# cfs_5.net
KiCad netlist of a schematic drawn in EAGLE
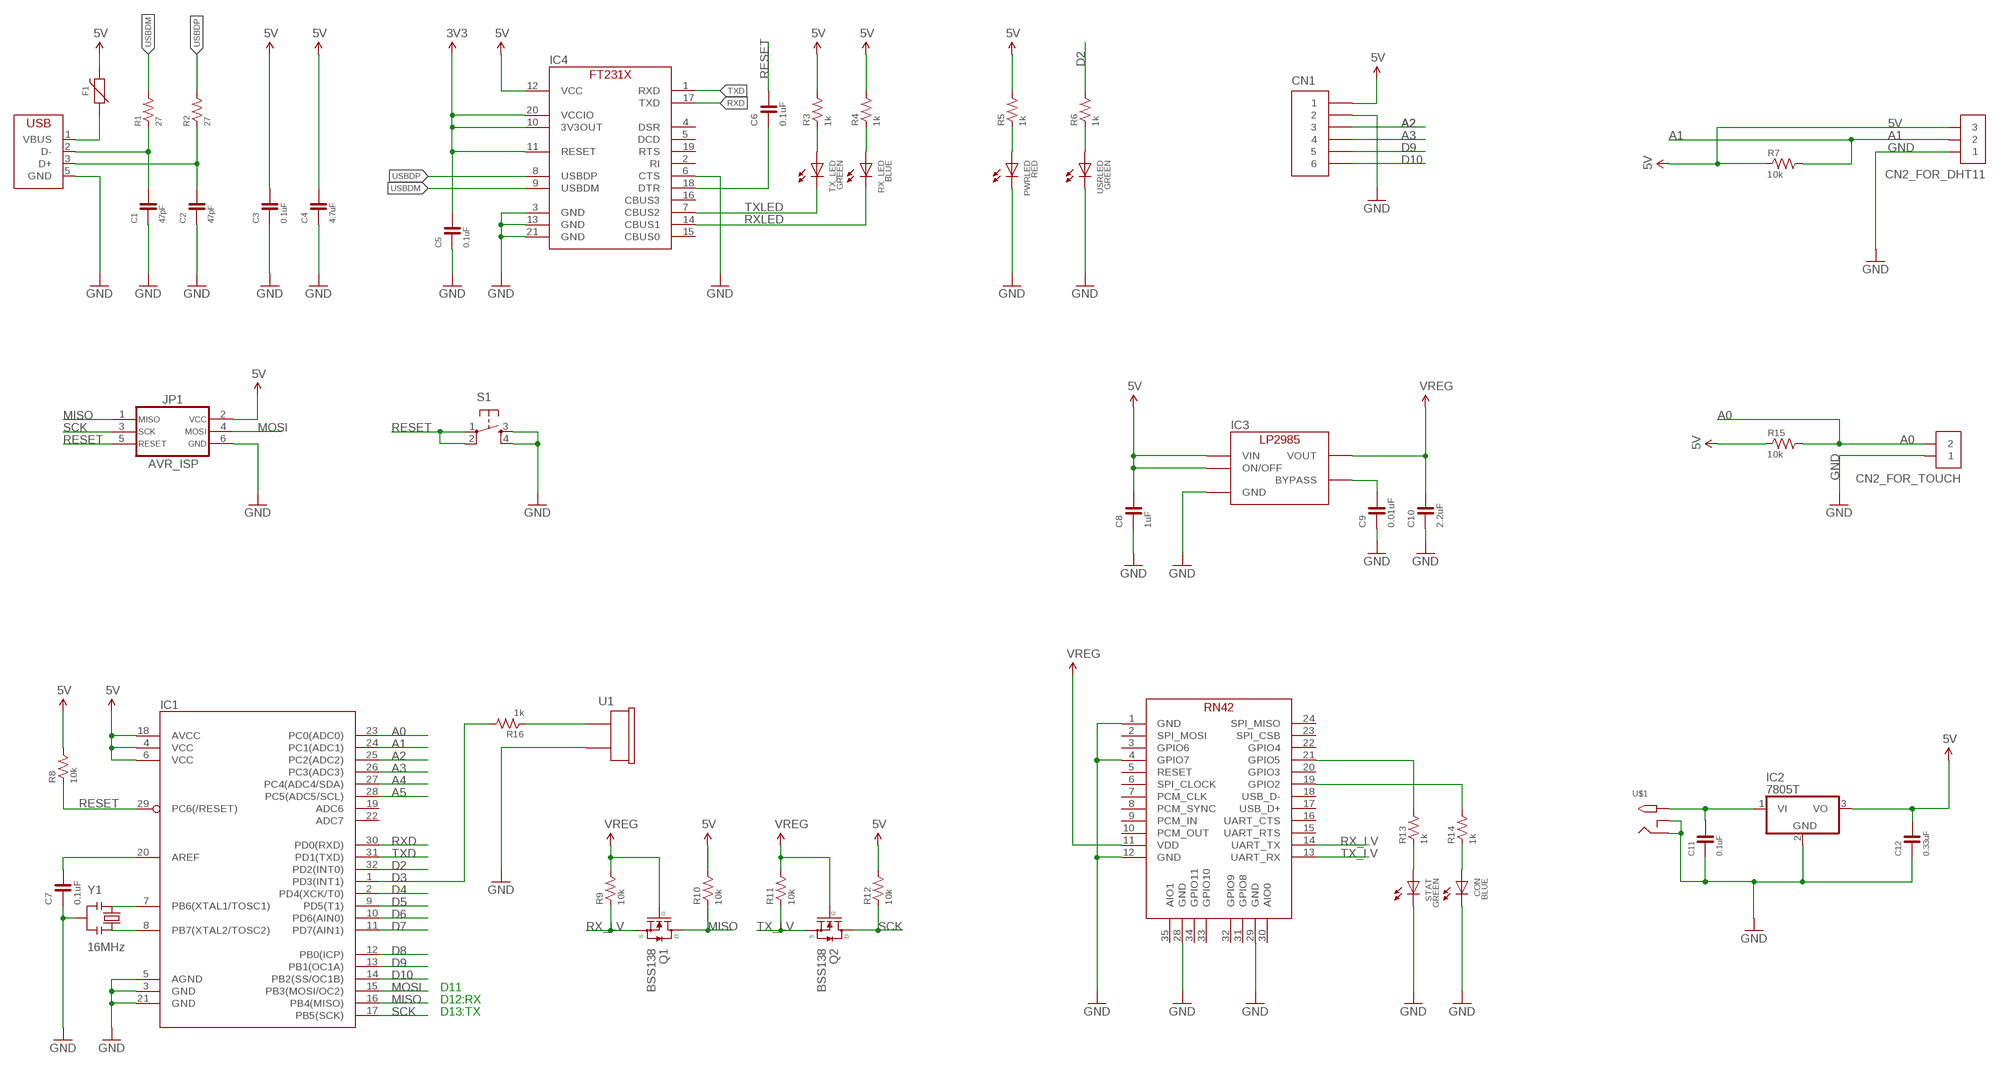
[diagram p0: schematic, sheet 1]

(export (version "E")
  (design (tool "Eeschema 10.0.6"))
  (components
    (comp (ref "C1")
      (value "47pF")
      (footprint "eagle-import:EIA0603")
      (libsource (lib "eagle-import") (part "u-aizu_CAPACITOR-0603"))
    )
    (comp (ref "C2")
      (value "47pF")
      (footprint "eagle-import:EIA0603")
      (libsource (lib "eagle-import") (part "u-aizu_CAPACITOR-0603"))
    )
    (comp (ref "C3")
      (value "0.1uF")
      (footprint "eagle-import:EIA0603")
      (libsource (lib "eagle-import") (part "u-aizu_CAPACITOR-0603"))
    )
    (comp (ref "C4")
      (value "4.7uF")
      (footprint "eagle-import:EIA0603")
      (libsource (lib "eagle-import") (part "u-aizu_CAPACITOR-0603"))
    )
    (comp (ref "C5")
      (value "0.1uF")
      (footprint "eagle-import:EIA0603")
      (libsource (lib "eagle-import") (part "u-aizu_CAPACITOR-0603"))
    )
    (comp (ref "C6")
      (value "0.1uF")
      (footprint "eagle-import:0603")
      (libsource (lib "eagle-import") (part "CAPACITOR-0603"))
    )
    (comp (ref "C7")
      (value "0.1uF")
      (footprint "eagle-import:0603")
      (libsource (lib "eagle-import") (part "CAPACITOR-0603"))
    )
    (comp (ref "C8")
      (value "1uF")
      (footprint "eagle-import:0603")
      (libsource (lib "eagle-import") (part "CAPACITOR-0603"))
    )
    (comp (ref "C9")
      (value "0.01uF")
      (footprint "eagle-import:0603")
      (libsource (lib "eagle-import") (part "CAPACITOR-0603"))
    )
    (comp (ref "C10")
      (value "2.2uF")
      (footprint "eagle-import:0603")
      (libsource (lib "eagle-import") (part "CAPACITOR-0603"))
    )
    (comp (ref "C11")
      (value "0.1uF")
      (footprint "eagle-import:EIA0603")
      (libsource (lib "eagle-import") (part "u-aizu_CAPACITOR-0603"))
    )
    (comp (ref "C12")
      (value "0.33uF")
      (footprint "eagle-import:EIA0603")
      (libsource (lib "eagle-import") (part "u-aizu_CAPACITOR-0603"))
    )
    (comp (ref "CN1")
      (value "PIN_HEADER_1X6")
      (footprint "eagle-import:PIN_1X6")
      (libsource (lib "eagle-import") (part "PIN_HEADER_1X6"))
    )
    (comp (ref "CN2_FOR_DHT11")
      (value "PIN_HEADER_1X3")
      (footprint "eagle-import:PIN_1X3")
      (libsource (lib "eagle-import") (part "PIN_HEADER_1X3"))
    )
    (comp (ref "CN2_FOR_TOUCH")
      (value "PIN_HEADER_1X2")
      (footprint "eagle-import:PIN_1X2")
      (libsource (lib "eagle-import") (part "PIN_HEADER_1X2"))
    )
    (comp (ref "CON")
      (value "BLUE")
      (footprint "eagle-import:0603")
      (libsource (lib "eagle-import") (part "LED-0603"))
    )
    (comp (ref "F1")
      (value "FUSE-NANO")
      (footprint "eagle-import:NANOSMDC035F")
      (libsource (lib "eagle-import") (part "FUSE-NANO"))
    )
    (comp (ref "IC1")
      (value "ATMEGA328P-AU")
      (footprint "eagle-import:TQFP-32")
      (libsource (lib "eagle-import") (part "ATMEGA328P-AU"))
    )
    (comp (ref "IC2")
      (value "7805T")
      (footprint "eagle-import:TO220H")
      (libsource (lib "eagle-import") (part "78T05"))
    )
    (comp (ref "IC3")
      (value "LP2985-33DBV")
      (footprint "eagle-import:SOT-23-5")
      (libsource (lib "eagle-import") (part "LP2985-33DBV"))
    )
    (comp (ref "IC4")
      (value "FT231XQ")
      (footprint "eagle-import:QFN-20_FT231X")
      (libsource (lib "eagle-import") (part "FT231XQ"))
    )
    (comp (ref "JP1")
      (value "AVR_ISP")
      (footprint "eagle-import:TC2030")
      (libsource (lib "eagle-import") (part "AVR_ISP-TC2030_NOHOLE"))
    )
    (comp (ref "PWRLED")
      (value "RED")
      (footprint "eagle-import:0603")
      (libsource (lib "eagle-import") (part "LED-0603"))
    )
    (comp (ref "Q1")
      (value "BSS138")
      (footprint "eagle-import:SOT23-3")
      (libsource (lib "eagle-import") (part "MOSFET-N"))
    )
    (comp (ref "Q2")
      (value "BSS138")
      (footprint "eagle-import:SOT23-3")
      (libsource (lib "eagle-import") (part "MOSFET-N"))
    )
    (comp (ref "R1")
      (value "27")
      (footprint "eagle-import:EIA0603")
      (libsource (lib "eagle-import") (part "u-aizu_RESISTOR-0603"))
    )
    (comp (ref "R2")
      (value "27")
      (footprint "eagle-import:EIA0603")
      (libsource (lib "eagle-import") (part "u-aizu_RESISTOR-0603"))
    )
    (comp (ref "R3")
      (value "1k")
      (footprint "eagle-import:0603")
      (libsource (lib "eagle-import") (part "RESISTOR-0603"))
    )
    (comp (ref "R4")
      (value "1k")
      (footprint "eagle-import:0603")
      (libsource (lib "eagle-import") (part "RESISTOR-0603"))
    )
    (comp (ref "R5")
      (value "1k")
      (footprint "eagle-import:0603")
      (libsource (lib "eagle-import") (part "RESISTOR-0603"))
    )
    (comp (ref "R6")
      (value "1k")
      (footprint "eagle-import:0603")
      (libsource (lib "eagle-import") (part "RESISTOR-0603"))
    )
    (comp (ref "R7")
      (value "10k")
      (footprint "eagle-import:0603")
      (libsource (lib "eagle-import") (part "RESISTOR-0603"))
    )
    (comp (ref "R8")
      (value "10k")
      (footprint "eagle-import:0603")
      (libsource (lib "eagle-import") (part "RESISTOR-0603"))
    )
    (comp (ref "R9")
      (value "10k")
      (footprint "eagle-import:0603")
      (libsource (lib "eagle-import") (part "RESISTOR-0603"))
    )
    (comp (ref "R10")
      (value "10k")
      (footprint "eagle-import:0603")
      (libsource (lib "eagle-import") (part "RESISTOR-0603"))
    )
    (comp (ref "R11")
      (value "10k")
      (footprint "eagle-import:0603")
      (libsource (lib "eagle-import") (part "RESISTOR-0603"))
    )
    (comp (ref "R12")
      (value "10k")
      (footprint "eagle-import:0603")
      (libsource (lib "eagle-import") (part "RESISTOR-0603"))
    )
    (comp (ref "R13")
      (value "1k")
      (footprint "eagle-import:0603")
      (libsource (lib "eagle-import") (part "RESISTOR-0603"))
    )
    (comp (ref "R14")
      (value "1k")
      (footprint "eagle-import:0603")
      (libsource (lib "eagle-import") (part "RESISTOR-0603"))
    )
    (comp (ref "R15")
      (value "10k")
      (footprint "eagle-import:0603")
      (libsource (lib "eagle-import") (part "RESISTOR-0603"))
    )
    (comp (ref "R16")
      (value "1k")
      (footprint "eagle-import:0603")
      (libsource (lib "eagle-import") (part "RESISTOR-0603"))
    )
    (comp (ref "RX_LED")
      (value "BLUE")
      (footprint "eagle-import:0603")
      (libsource (lib "eagle-import") (part "LED-0603"))
    )
    (comp (ref "S1")
      (value "TACT-SWITCH-SMD_KMR2")
      (footprint "eagle-import:KMR2")
      (libsource (lib "eagle-import") (part "TACT-SWITCH-SMD_KMR2"))
    )
    (comp (ref "STAT")
      (value "GREEN")
      (footprint "eagle-import:0603")
      (libsource (lib "eagle-import") (part "LED-0603"))
    )
    (comp (ref "TX_LED")
      (value "GREEN")
      (footprint "eagle-import:0603")
      (libsource (lib "eagle-import") (part "LED-0603"))
    )
    (comp (ref "U$1")
      (value "2.1MMJACKTHM")
      (footprint "eagle-import:PJ-102A")
      (libsource (lib "eagle-import") (part "2.1MMJACKTHM"))
    )
    (comp (ref "U$4")
      (value "MICROCHIP-RN42")
      (footprint "eagle-import:MICROCHIP-RN42")
      (libsource (lib "eagle-import") (part "MICROCHIP-RN42"))
    )
    (comp (ref "U1")
      (value "BUZZER")
      (footprint "eagle-import:PKM13EPYH4000-A0")
      (libsource (lib "eagle-import") (part "BUZZER"))
    )
    (comp (ref "USB1")
      (value "USB-MICRO_B_SMT_HIROSE")
      (footprint "eagle-import:ZX62R-B-5P")
      (libsource (lib "eagle-import") (part "USB-MICRO_B_SMT_HIROSE"))
    )
    (comp (ref "USRLED")
      (value "GREEN")
      (footprint "eagle-import:0603")
      (libsource (lib "eagle-import") (part "LED-0603"))
    )
    (comp (ref "Y1")
      (value "16MHz")
      (footprint "eagle-import:CSTCE_V")
      (libsource (lib "eagle-import") (part "RESONATOR-CSTCE_V"))
    )
  )
  (nets
    (net (code "1") (name "/A0") (class "Default")
      (node (ref "CN2_FOR_TOUCH") (pin "2") (pinfunction "2_2") (pintype "bidirectional"))
      (node (ref "IC1") (pin "23") (pinfunction "PC0(ADC0)_23") (pintype "bidirectional"))
      (node (ref "R15") (pin "2") (pinfunction "2_2") (pintype "bidirectional"))
    )
    (net (code "2") (name "/A1") (class "Default")
      (node (ref "CN2_FOR_DHT11") (pin "2") (pinfunction "2_2") (pintype "bidirectional"))
      (node (ref "IC1") (pin "24") (pinfunction "PC1(ADC1)_24") (pintype "bidirectional"))
      (node (ref "R7") (pin "2") (pinfunction "2_2") (pintype "bidirectional"))
    )
    (net (code "3") (name "/A2") (class "Default")
      (node (ref "CN1") (pin "3") (pinfunction "3_3") (pintype "bidirectional"))
      (node (ref "IC1") (pin "25") (pinfunction "PC2(ADC2)_25") (pintype "bidirectional"))
    )
    (net (code "4") (name "/A3") (class "Default")
      (node (ref "CN1") (pin "4") (pinfunction "4_4") (pintype "bidirectional"))
      (node (ref "IC1") (pin "26") (pinfunction "PC3(ADC3)_26") (pintype "bidirectional"))
    )
    (net (code "5") (name "/A4") (class "Default")
      (node (ref "IC1") (pin "27") (pinfunction "PC4(ADC4/SDA)_27") (pintype "bidirectional"))
    )
    (net (code "6") (name "/A5") (class "Default")
      (node (ref "IC1") (pin "28") (pinfunction "PC5(ADC5/SCL)_28") (pintype "bidirectional"))
    )
    (net (code "7") (name "/D2") (class "Default")
      (node (ref "IC1") (pin "32") (pinfunction "PD2(INT0)_32") (pintype "bidirectional"))
      (node (ref "R6") (pin "2") (pinfunction "2_2") (pintype "bidirectional"))
    )
    (net (code "8") (name "/D3") (class "Default")
      (node (ref "IC1") (pin "1") (pinfunction "PD3(INT1)_1") (pintype "bidirectional"))
      (node (ref "R16") (pin "2") (pinfunction "2_2") (pintype "bidirectional"))
    )
    (net (code "9") (name "/D4") (class "Default")
      (node (ref "IC1") (pin "2") (pinfunction "PD4(XCK/T0)_2") (pintype "bidirectional"))
    )
    (net (code "10") (name "/D5") (class "Default")
      (node (ref "IC1") (pin "9") (pinfunction "PD5(T1)_9") (pintype "bidirectional"))
    )
    (net (code "11") (name "/D6") (class "Default")
      (node (ref "IC1") (pin "10") (pinfunction "PD6(AIN0)_10") (pintype "bidirectional"))
    )
    (net (code "12") (name "/D7") (class "Default")
      (node (ref "IC1") (pin "11") (pinfunction "PD7(AIN1)_11") (pintype "bidirectional"))
    )
    (net (code "13") (name "/D8") (class "Default")
      (node (ref "IC1") (pin "12") (pinfunction "PB0(ICP)_12") (pintype "bidirectional"))
    )
    (net (code "14") (name "/D9") (class "Default")
      (node (ref "CN1") (pin "5") (pinfunction "5_5") (pintype "bidirectional"))
      (node (ref "IC1") (pin "13") (pinfunction "PB1(OC1A)_13") (pintype "bidirectional"))
    )
    (net (code "15") (name "/D10") (class "Default")
      (node (ref "CN1") (pin "6") (pinfunction "6_6") (pintype "bidirectional"))
      (node (ref "IC1") (pin "14") (pinfunction "PB2(SS/OC1B)_14") (pintype "bidirectional"))
    )
    (net (code "16") (name "/MISO") (class "Default")
      (node (ref "IC1") (pin "16") (pinfunction "PB4(MISO)_16") (pintype "bidirectional"))
      (node (ref "JP1") (pin "1") (pinfunction "1_1") (pintype "passive"))
      (node (ref "Q1") (pin "3") (pinfunction "D_3") (pintype "passive"))
      (node (ref "R10") (pin "1") (pinfunction "1_1") (pintype "bidirectional"))
    )
    (net (code "17") (name "/MOSI") (class "Default")
      (node (ref "IC1") (pin "15") (pinfunction "PB3(MOSI/OC2)_15") (pintype "bidirectional"))
      (node (ref "JP1") (pin "4") (pinfunction "4_4") (pintype "passive"))
    )
    (net (code "18") (name "/RESET") (class "Default")
      (node (ref "C6") (pin "2") (pinfunction "2_2") (pintype "passive"))
      (node (ref "IC1") (pin "29") (pinfunction "PC6(/RESET)_29") (pintype "bidirectional"))
      (node (ref "JP1") (pin "5") (pinfunction "5_5") (pintype "passive"))
      (node (ref "R8") (pin "1") (pinfunction "1_1") (pintype "bidirectional"))
      (node (ref "S1") (pin "1") (pinfunction "1_1") (pintype "passive"))
      (node (ref "S1") (pin "2") (pinfunction "2_2") (pintype "passive"))
    )
    (net (code "19") (name "/RXLED") (class "Default")
      (node (ref "IC4") (pin "14") (pinfunction "CBUS1_14") (pintype "bidirectional"))
      (node (ref "RX_LED") (pin "CATHODE") (pinfunction "CATHODE_CATHODE") (pintype "passive"))
    )
    (net (code "20") (name "/RX_LV") (class "Default")
      (node (ref "Q1") (pin "2") (pinfunction "S_2") (pintype "passive"))
      (node (ref "R9") (pin "1") (pinfunction "1_1") (pintype "bidirectional"))
      (node (ref "U$4") (pin "14") (pinfunction "UART_TX_14") (pintype "bidirectional"))
    )
    (net (code "21") (name "/SCK") (class "Default")
      (node (ref "IC1") (pin "17") (pinfunction "PB5(SCK)_17") (pintype "bidirectional"))
      (node (ref "JP1") (pin "3") (pinfunction "3_3") (pintype "passive"))
      (node (ref "Q2") (pin "3") (pinfunction "D_3") (pintype "passive"))
      (node (ref "R12") (pin "1") (pinfunction "1_1") (pintype "bidirectional"))
    )
    (net (code "22") (name "/TXLED") (class "Default")
      (node (ref "IC4") (pin "7") (pinfunction "CBUS2_7") (pintype "bidirectional"))
      (node (ref "TX_LED") (pin "CATHODE") (pinfunction "CATHODE_CATHODE") (pintype "passive"))
    )
    (net (code "23") (name "/TX_LV") (class "Default")
      (node (ref "Q2") (pin "2") (pinfunction "S_2") (pintype "passive"))
      (node (ref "R11") (pin "1") (pinfunction "1_1") (pintype "bidirectional"))
      (node (ref "U$4") (pin "13") (pinfunction "UART_RX_13") (pintype "bidirectional"))
    )
    (net (code "24") (name "3V3") (class "Default")
      (node (ref "C5") (pin "2") (pinfunction "2_2") (pintype "passive"))
      (node (ref "IC4") (pin "10") (pinfunction "3V3OUT_10") (pintype "bidirectional"))
      (node (ref "IC4") (pin "11") (pinfunction "RESET_11") (pintype "bidirectional"))
      (node (ref "IC4") (pin "20") (pinfunction "VCCIO_20") (pintype "bidirectional"))
    )
    (net (code "25") (name "5V") (class "Default")
      (node (ref "C12") (pin "2") (pinfunction "2_2") (pintype "passive"))
      (node (ref "C3") (pin "2") (pinfunction "2_2") (pintype "passive"))
      (node (ref "C4") (pin "2") (pinfunction "2_2") (pintype "passive"))
      (node (ref "C8") (pin "2") (pinfunction "2_2") (pintype "passive"))
      (node (ref "CN1") (pin "1") (pinfunction "1_1") (pintype "bidirectional"))
      (node (ref "CN2_FOR_DHT11") (pin "3") (pinfunction "3_3") (pintype "bidirectional"))
      (node (ref "F1") (pin "2") (pinfunction "2_2") (pintype "bidirectional"))
      (node (ref "IC1") (pin "18") (pinfunction "AVCC_18") (pintype "bidirectional"))
      (node (ref "IC1") (pin "4") (pinfunction "VCC_4") (pintype "bidirectional"))
      (node (ref "IC1") (pin "6") (pinfunction "VCC_6") (pintype "bidirectional"))
      (node (ref "IC2") (pin "3") (pinfunction "VO_3") (pintype "passive"))
      (node (ref "IC3") (pin "1") (pinfunction "VIN_1") (pintype "input"))
      (node (ref "IC3") (pin "3") (pinfunction "ON/OFF_3") (pintype "input"))
      (node (ref "IC4") (pin "12") (pinfunction "VCC_12") (pintype "bidirectional"))
      (node (ref "JP1") (pin "2") (pinfunction "2_2") (pintype "passive"))
      (node (ref "R10") (pin "2") (pinfunction "2_2") (pintype "bidirectional"))
      (node (ref "R12") (pin "2") (pinfunction "2_2") (pintype "bidirectional"))
      (node (ref "R15") (pin "1") (pinfunction "1_1") (pintype "bidirectional"))
      (node (ref "R3") (pin "2") (pinfunction "2_2") (pintype "bidirectional"))
      (node (ref "R4") (pin "2") (pinfunction "2_2") (pintype "bidirectional"))
      (node (ref "R5") (pin "2") (pinfunction "2_2") (pintype "bidirectional"))
      (node (ref "R7") (pin "1") (pinfunction "1_1") (pintype "bidirectional"))
      (node (ref "R8") (pin "2") (pinfunction "2_2") (pintype "bidirectional"))
    )
    (net (code "26") (name "GND") (class "Default")
      (node (ref "C1") (pin "1") (pinfunction "1_1") (pintype "passive"))
      (node (ref "C10") (pin "1") (pinfunction "1_1") (pintype "passive"))
      (node (ref "C11") (pin "1") (pinfunction "1_1") (pintype "passive"))
      (node (ref "C12") (pin "1") (pinfunction "1_1") (pintype "passive"))
      (node (ref "C2") (pin "1") (pinfunction "1_1") (pintype "passive"))
      (node (ref "C3") (pin "1") (pinfunction "1_1") (pintype "passive"))
      (node (ref "C4") (pin "1") (pinfunction "1_1") (pintype "passive"))
      (node (ref "C5") (pin "1") (pinfunction "1_1") (pintype "passive"))
      (node (ref "C7") (pin "1") (pinfunction "1_1") (pintype "passive"))
      (node (ref "C8") (pin "1") (pinfunction "1_1") (pintype "passive"))
      (node (ref "C9") (pin "1") (pinfunction "1_1") (pintype "passive"))
      (node (ref "CN1") (pin "2") (pinfunction "2_2") (pintype "bidirectional"))
      (node (ref "CN2_FOR_DHT11") (pin "1") (pinfunction "1_1") (pintype "bidirectional"))
      (node (ref "CN2_FOR_TOUCH") (pin "1") (pinfunction "1_1") (pintype "bidirectional"))
      (node (ref "CON") (pin "CATHODE") (pinfunction "CATHODE_CATHODE") (pintype "passive"))
      (node (ref "IC1") (pin "21") (pinfunction "GND_21") (pintype "bidirectional"))
      (node (ref "IC1") (pin "3") (pinfunction "GND_3") (pintype "bidirectional"))
      (node (ref "IC1") (pin "5") (pinfunction "AGND_5") (pintype "bidirectional"))
      (node (ref "IC2") (pin "2") (pinfunction "GND_2") (pintype "passive"))
      (node (ref "IC3") (pin "2") (pinfunction "GND_2") (pintype "power_in"))
      (node (ref "IC4") (pin "13") (pinfunction "GND_13") (pintype "bidirectional"))
      (node (ref "IC4") (pin "21") (pinfunction "GND_21") (pintype "bidirectional"))
      (node (ref "IC4") (pin "3") (pinfunction "GND_3") (pintype "bidirectional"))
      (node (ref "IC4") (pin "6") (pinfunction "CTS_6") (pintype "bidirectional"))
      (node (ref "JP1") (pin "6") (pinfunction "6_6") (pintype "passive"))
      (node (ref "PWRLED") (pin "CATHODE") (pinfunction "CATHODE_CATHODE") (pintype "passive"))
      (node (ref "S1") (pin "3") (pinfunction "3_3") (pintype "passive"))
      (node (ref "S1") (pin "4") (pinfunction "4_4") (pintype "passive"))
      (node (ref "STAT") (pin "CATHODE") (pinfunction "CATHODE_CATHODE") (pintype "passive"))
      (node (ref "U$1") (pin "RING") (pinfunction "RING_RING") (pintype "bidirectional"))
      (node (ref "U$1") (pin "RING_SW") (pinfunction "RING_SW_RING_SW") (pintype "bidirectional"))
      (node (ref "U$4") (pin "1") (pinfunction "GND_1") (pintype "bidirectional"))
      (node (ref "U$4") (pin "12") (pinfunction "GND_12") (pintype "bidirectional"))
      (node (ref "U$4") (pin "28") (pinfunction "GND_28") (pintype "bidirectional"))
      (node (ref "U$4") (pin "29") (pinfunction "GND_29") (pintype "bidirectional"))
      (node (ref "U$4") (pin "4") (pinfunction "GPIO7_4") (pintype "bidirectional"))
      (node (ref "U1") (pin "2") (pinfunction "2_2") (pintype "passive"))
      (node (ref "USB1") (pin "5") (pinfunction "GND_5") (pintype "bidirectional"))
      (node (ref "USRLED") (pin "CATHODE") (pinfunction "CATHODE_CATHODE") (pintype "passive"))
      (node (ref "Y1") (pin "2") (pinfunction "2_2") (pintype "passive"))
    )
    (net (code "27") (name "Net-(CON-PadANODE)") (class "Default")
      (node (ref "CON") (pin "ANODE") (pinfunction "ANODE_ANODE") (pintype "passive"))
      (node (ref "R14") (pin "1") (pinfunction "1_1") (pintype "bidirectional"))
    )
    (net (code "28") (name "Net-(IC1-AREF)") (class "Default")
      (node (ref "C7") (pin "2") (pinfunction "2_2") (pintype "passive"))
      (node (ref "IC1") (pin "20") (pinfunction "AREF_20") (pintype "bidirectional"))
    )
    (net (code "29") (name "Net-(IC1-PB6(XTAL1{slash}TOSC1))") (class "Default")
      (node (ref "IC1") (pin "7") (pinfunction "PB6(XTAL1/TOSC1)_7") (pintype "bidirectional"))
      (node (ref "Y1") (pin "1") (pinfunction "1_1") (pintype "passive"))
    )
    (net (code "30") (name "Net-(IC1-PB7(XTAL2{slash}TOSC2))") (class "Default")
      (node (ref "IC1") (pin "8") (pinfunction "PB7(XTAL2/TOSC2)_8") (pintype "bidirectional"))
      (node (ref "Y1") (pin "3") (pinfunction "3_3") (pintype "passive"))
    )
    (net (code "31") (name "Net-(IC2-VI)") (class "Default")
      (node (ref "C11") (pin "2") (pinfunction "2_2") (pintype "passive"))
      (node (ref "IC2") (pin "1") (pinfunction "VI_1") (pintype "input"))
      (node (ref "U$1") (pin "TIP") (pinfunction "TIP_TIP") (pintype "bidirectional"))
    )
    (net (code "32") (name "Net-(IC3-BYPASS)") (class "Default")
      (node (ref "C9") (pin "2") (pinfunction "2_2") (pintype "passive"))
      (node (ref "IC3") (pin "4") (pinfunction "BYPASS_4") (pintype "bidirectional"))
    )
    (net (code "33") (name "Net-(IC4-DTR)") (class "Default")
      (node (ref "C6") (pin "1") (pinfunction "1_1") (pintype "passive"))
      (node (ref "IC4") (pin "18") (pinfunction "DTR_18") (pintype "bidirectional"))
    )
    (net (code "34") (name "Net-(PWRLED-PadANODE)") (class "Default")
      (node (ref "PWRLED") (pin "ANODE") (pinfunction "ANODE_ANODE") (pintype "passive"))
      (node (ref "R5") (pin "1") (pinfunction "1_1") (pintype "bidirectional"))
    )
    (net (code "35") (name "Net-(R3-Pad1)") (class "Default")
      (node (ref "R3") (pin "1") (pinfunction "1_1") (pintype "bidirectional"))
      (node (ref "TX_LED") (pin "ANODE") (pinfunction "ANODE_ANODE") (pintype "passive"))
    )
    (net (code "36") (name "Net-(R4-Pad1)") (class "Default")
      (node (ref "R4") (pin "1") (pinfunction "1_1") (pintype "bidirectional"))
      (node (ref "RX_LED") (pin "ANODE") (pinfunction "ANODE_ANODE") (pintype "passive"))
    )
    (net (code "37") (name "Net-(R6-Pad1)") (class "Default")
      (node (ref "R6") (pin "1") (pinfunction "1_1") (pintype "bidirectional"))
      (node (ref "USRLED") (pin "ANODE") (pinfunction "ANODE_ANODE") (pintype "passive"))
    )
    (net (code "38") (name "Net-(R13-Pad1)") (class "Default")
      (node (ref "R13") (pin "1") (pinfunction "1_1") (pintype "bidirectional"))
      (node (ref "STAT") (pin "ANODE") (pinfunction "ANODE_ANODE") (pintype "passive"))
    )
    (net (code "39") (name "Net-(R16-Pad1)") (class "Default")
      (node (ref "R16") (pin "1") (pinfunction "1_1") (pintype "bidirectional"))
      (node (ref "U1") (pin "1") (pinfunction "1_1") (pintype "passive"))
    )
    (net (code "40") (name "Net-(U$4-GPIO2)") (class "Default")
      (node (ref "R14") (pin "2") (pinfunction "2_2") (pintype "bidirectional"))
      (node (ref "U$4") (pin "19") (pinfunction "GPIO2_19") (pintype "bidirectional"))
    )
    (net (code "41") (name "Net-(U$4-GPIO5)") (class "Default")
      (node (ref "R13") (pin "2") (pinfunction "2_2") (pintype "bidirectional"))
      (node (ref "U$4") (pin "21") (pinfunction "GPIO5_21") (pintype "bidirectional"))
    )
    (net (code "42") (name "Net-(USB1-D+)") (class "Default")
      (node (ref "C2") (pin "2") (pinfunction "2_2") (pintype "passive"))
      (node (ref "R2") (pin "1") (pinfunction "1_1") (pintype "bidirectional"))
      (node (ref "USB1") (pin "3") (pinfunction "D+_3") (pintype "bidirectional"))
    )
    (net (code "43") (name "Net-(USB1-D-)") (class "Default")
      (node (ref "C1") (pin "2") (pinfunction "2_2") (pintype "passive"))
      (node (ref "R1") (pin "1") (pinfunction "1_1") (pintype "bidirectional"))
      (node (ref "USB1") (pin "2") (pinfunction "D-_2") (pintype "bidirectional"))
    )
    (net (code "44") (name "Net-(USB1-VBUS)") (class "Default")
      (node (ref "F1") (pin "1") (pinfunction "1_1") (pintype "bidirectional"))
      (node (ref "USB1") (pin "1") (pinfunction "VBUS_1") (pintype "bidirectional"))
    )
    (net (code "45") (name "RXD") (class "Default")
      (node (ref "IC1") (pin "30") (pinfunction "PD0(RXD)_30") (pintype "bidirectional"))
      (node (ref "IC4") (pin "17") (pinfunction "TXD_17") (pintype "bidirectional"))
    )
    (net (code "46") (name "TXD") (class "Default")
      (node (ref "IC1") (pin "31") (pinfunction "PD1(TXD)_31") (pintype "bidirectional"))
      (node (ref "IC4") (pin "1") (pinfunction "RXD_1") (pintype "bidirectional"))
    )
    (net (code "47") (name "USBDM") (class "Default")
      (node (ref "IC4") (pin "9") (pinfunction "USBDM_9") (pintype "bidirectional"))
      (node (ref "R1") (pin "2") (pinfunction "2_2") (pintype "bidirectional"))
    )
    (net (code "48") (name "USBDP") (class "Default")
      (node (ref "IC4") (pin "8") (pinfunction "USBDP_8") (pintype "bidirectional"))
      (node (ref "R2") (pin "2") (pinfunction "2_2") (pintype "bidirectional"))
    )
    (net (code "49") (name "VREG") (class "Default")
      (node (ref "C10") (pin "2") (pinfunction "2_2") (pintype "passive"))
      (node (ref "IC3") (pin "5") (pinfunction "VOUT_5") (pintype "output"))
      (node (ref "Q1") (pin "1") (pinfunction "G_1") (pintype "passive"))
      (node (ref "Q2") (pin "1") (pinfunction "G_1") (pintype "passive"))
      (node (ref "R11") (pin "2") (pinfunction "2_2") (pintype "bidirectional"))
      (node (ref "R9") (pin "2") (pinfunction "2_2") (pintype "bidirectional"))
      (node (ref "U$4") (pin "11") (pinfunction "VDD_11") (pintype "bidirectional"))
    )
    (net (code "50") (name "unconnected-(IC1-ADC6-Pad19)") (class "Default")
      (node (ref "IC1") (pin "19") (pinfunction "ADC6_19") (pintype "bidirectional"))
    )
    (net (code "51") (name "unconnected-(IC1-ADC7-Pad22)") (class "Default")
      (node (ref "IC1") (pin "22") (pinfunction "ADC7_22") (pintype "bidirectional"))
    )
    (net (code "52") (name "unconnected-(IC4-CBUS0-Pad15)") (class "Default")
      (node (ref "IC4") (pin "15") (pinfunction "CBUS0_15") (pintype "bidirectional"))
    )
    (net (code "53") (name "unconnected-(IC4-CBUS3-Pad16)") (class "Default")
      (node (ref "IC4") (pin "16") (pinfunction "CBUS3_16") (pintype "bidirectional"))
    )
    (net (code "54") (name "unconnected-(IC4-DCD-Pad5)") (class "Default")
      (node (ref "IC4") (pin "5") (pinfunction "DCD_5") (pintype "bidirectional"))
    )
    (net (code "55") (name "unconnected-(IC4-DSR-Pad4)") (class "Default")
      (node (ref "IC4") (pin "4") (pinfunction "DSR_4") (pintype "bidirectional"))
    )
    (net (code "56") (name "unconnected-(IC4-RI-Pad2)") (class "Default")
      (node (ref "IC4") (pin "2") (pinfunction "RI_2") (pintype "bidirectional"))
    )
    (net (code "57") (name "unconnected-(IC4-RTS-Pad19)") (class "Default")
      (node (ref "IC4") (pin "19") (pinfunction "RTS_19") (pintype "bidirectional"))
    )
    (net (code "58") (name "unconnected-(U$4-AIO0-Pad30)") (class "Default")
      (node (ref "U$4") (pin "30") (pinfunction "AIO0_30") (pintype "bidirectional"))
    )
    (net (code "59") (name "unconnected-(U$4-AIO1-Pad35)") (class "Default")
      (node (ref "U$4") (pin "35") (pinfunction "AIO1_35") (pintype "bidirectional"))
    )
    (net (code "60") (name "unconnected-(U$4-GPIO3-Pad20)") (class "Default")
      (node (ref "U$4") (pin "20") (pinfunction "GPIO3_20") (pintype "bidirectional"))
    )
    (net (code "61") (name "unconnected-(U$4-GPIO4-Pad22)") (class "Default")
      (node (ref "U$4") (pin "22") (pinfunction "GPIO4_22") (pintype "bidirectional"))
    )
    (net (code "62") (name "unconnected-(U$4-GPIO6-Pad3)") (class "Default")
      (node (ref "U$4") (pin "3") (pinfunction "GPIO6_3") (pintype "bidirectional"))
    )
    (net (code "63") (name "unconnected-(U$4-GPIO8-Pad31)") (class "Default")
      (node (ref "U$4") (pin "31") (pinfunction "GPIO8_31") (pintype "bidirectional"))
    )
    (net (code "64") (name "unconnected-(U$4-GPIO9-Pad32)") (class "Default")
      (node (ref "U$4") (pin "32") (pinfunction "GPIO9_32") (pintype "bidirectional"))
    )
    (net (code "65") (name "unconnected-(U$4-GPIO10-Pad33)") (class "Default")
      (node (ref "U$4") (pin "33") (pinfunction "GPIO10_33") (pintype "bidirectional"))
    )
    (net (code "66") (name "unconnected-(U$4-GPIO11-Pad34)") (class "Default")
      (node (ref "U$4") (pin "34") (pinfunction "GPIO11_34") (pintype "bidirectional"))
    )
    (net (code "67") (name "unconnected-(U$4-PCM_CLK-Pad7)") (class "Default")
      (node (ref "U$4") (pin "7") (pinfunction "PCM_CLK_7") (pintype "bidirectional"))
    )
    (net (code "68") (name "unconnected-(U$4-PCM_IN-Pad9)") (class "Default")
      (node (ref "U$4") (pin "9") (pinfunction "PCM_IN_9") (pintype "bidirectional"))
    )
    (net (code "69") (name "unconnected-(U$4-PCM_OUT-Pad10)") (class "Default")
      (node (ref "U$4") (pin "10") (pinfunction "PCM_OUT_10") (pintype "bidirectional"))
    )
    (net (code "70") (name "unconnected-(U$4-PCM_SYNC-Pad8)") (class "Default")
      (node (ref "U$4") (pin "8") (pinfunction "PCM_SYNC_8") (pintype "bidirectional"))
    )
    (net (code "71") (name "unconnected-(U$4-RESET-Pad5)") (class "Default")
      (node (ref "U$4") (pin "5") (pinfunction "RESET_5") (pintype "bidirectional"))
    )
    (net (code "72") (name "unconnected-(U$4-SPI_CLOCK-Pad6)") (class "Default")
      (node (ref "U$4") (pin "6") (pinfunction "SPI_CLOCK_6") (pintype "bidirectional"))
    )
    (net (code "73") (name "unconnected-(U$4-SPI_CSB-Pad23)") (class "Default")
      (node (ref "U$4") (pin "23") (pinfunction "SPI_CSB_23") (pintype "bidirectional"))
    )
    (net (code "74") (name "unconnected-(U$4-SPI_MISO-Pad24)") (class "Default")
      (node (ref "U$4") (pin "24") (pinfunction "SPI_MISO_24") (pintype "bidirectional"))
    )
    (net (code "75") (name "unconnected-(U$4-SPI_MOSI-Pad2)") (class "Default")
      (node (ref "U$4") (pin "2") (pinfunction "SPI_MOSI_2") (pintype "bidirectional"))
    )
    (net (code "76") (name "unconnected-(U$4-UART_CTS-Pad16)") (class "Default")
      (node (ref "U$4") (pin "16") (pinfunction "UART_CTS_16") (pintype "bidirectional"))
    )
    (net (code "77") (name "unconnected-(U$4-UART_RTS-Pad15)") (class "Default")
      (node (ref "U$4") (pin "15") (pinfunction "UART_RTS_15") (pintype "bidirectional"))
    )
    (net (code "78") (name "unconnected-(U$4-USB_D+-Pad17)") (class "Default")
      (node (ref "U$4") (pin "17") (pinfunction "USB_D+_17") (pintype "bidirectional"))
    )
    (net (code "79") (name "unconnected-(U$4-USB_D--Pad18)") (class "Default")
      (node (ref "U$4") (pin "18") (pinfunction "USB_D-_18") (pintype "bidirectional"))
    )
  )
)
